# Qwiic_Alphanumeric_Display.net
KiCad netlist of a schematic drawn in EAGLE
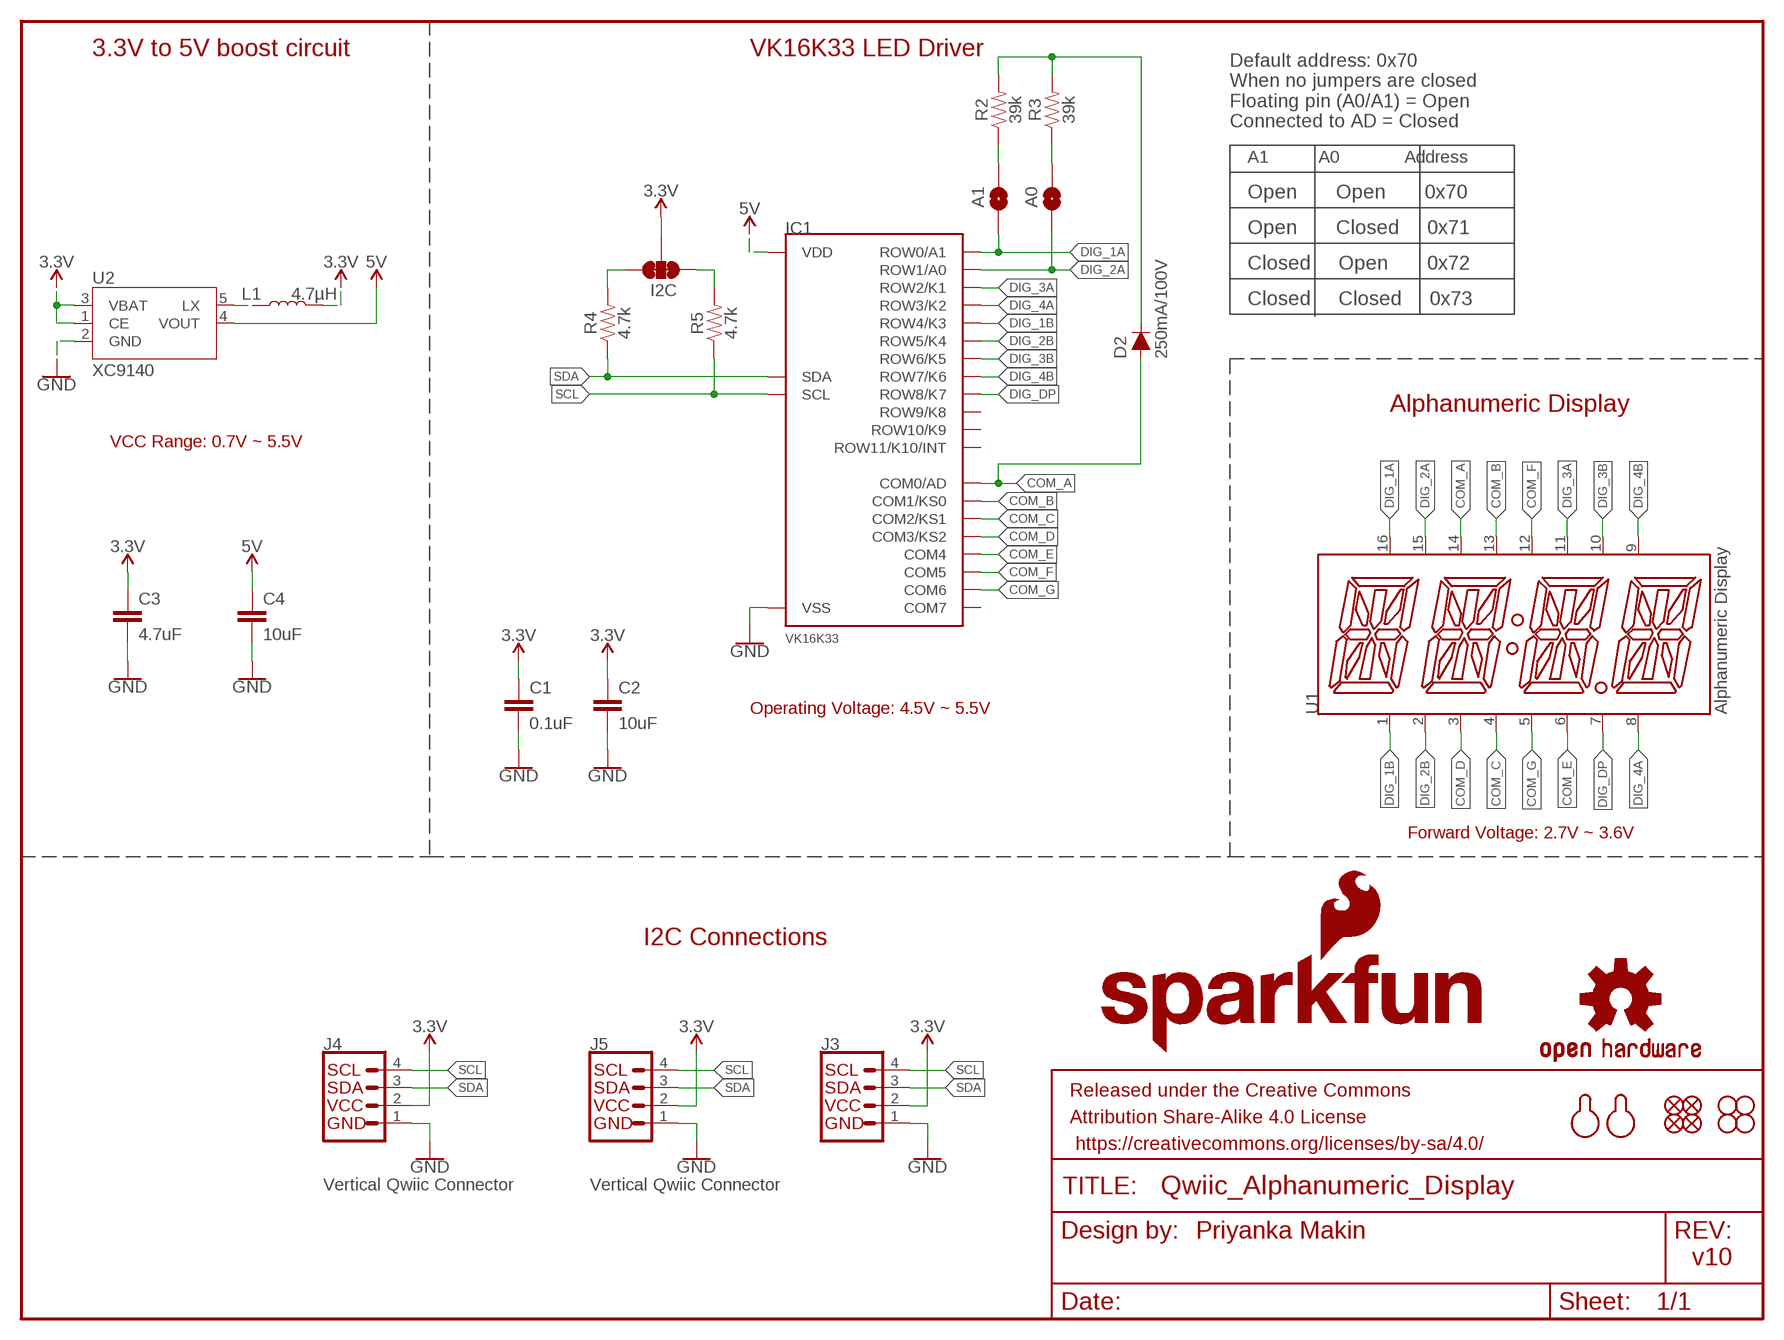
[diagram p0: schematic, sheet 1]

(export (version "E")
  (design (tool "Eeschema 10.0.6"))
  (components
    (comp (ref "A0")
      (value "JUMPER-SMT_2_NO_SILK")
      (footprint "eagle-import:SMT-JUMPER_2_NO_SILK")
      (libsource (lib "eagle-import") (part "JUMPER-SMT_2_NO_SILK"))
    )
    (comp (ref "A1")
      (value "JUMPER-SMT_2_NO_SILK")
      (footprint "eagle-import:SMT-JUMPER_2_NO_SILK")
      (libsource (lib "eagle-import") (part "JUMPER-SMT_2_NO_SILK"))
    )
    (comp (ref "C1")
      (value "0.1uF")
      (footprint "eagle-import:0603")
      (libsource (lib "eagle-import") (part "0.1UF-0603-25V-5%"))
    )
    (comp (ref "C2")
      (value "10uF")
      (footprint "eagle-import:0603")
      (libsource (lib "eagle-import") (part "10UF-0603-6.3V-20%"))
    )
    (comp (ref "C3")
      (value "4.7uF")
      (footprint "eagle-import:0603")
      (libsource (lib "eagle-import") (part "4.7UF-0603-6.3V-(10%)"))
    )
    (comp (ref "C4")
      (value "10uF")
      (footprint "eagle-import:0603")
      (libsource (lib "eagle-import") (part "10UF-0603-6.3V-20%"))
    )
    (comp (ref "D2")
      (value "250mA/100V")
      (footprint "eagle-import:SOD-323")
      (libsource (lib "eagle-import") (part "DIODE-BAS16J"))
    )
    (comp (ref "FD1")
      (value "FIDUCIAL1X2")
      (footprint "eagle-import:FIDUCIAL-1X2")
      (libsource (lib "eagle-import") (part "FIDUCIAL1X2"))
    )
    (comp (ref "FD2")
      (value "FIDUCIAL1X2")
      (footprint "eagle-import:FIDUCIAL-1X2")
      (libsource (lib "eagle-import") (part "FIDUCIAL1X2"))
    )
    (comp (ref "FD3")
      (value "FIDUCIAL1X2")
      (footprint "eagle-import:FIDUCIAL-1X2")
      (libsource (lib "eagle-import") (part "FIDUCIAL1X2"))
    )
    (comp (ref "FD4")
      (value "FIDUCIAL1X2")
      (footprint "eagle-import:FIDUCIAL-1X2")
      (libsource (lib "eagle-import") (part "FIDUCIAL1X2"))
    )
    (comp (ref "FRAME1")
      (value "FRAME-LETTER")
      (footprint "eagle-import:CREATIVE_COMMONS")
      (libsource (lib "eagle-import") (part "FRAME-LETTER"))
    )
    (comp (ref "H1")
      (value "STAND-OFF")
      (footprint "eagle-import:STAND-OFF")
      (libsource (lib "eagle-import") (part "STAND-OFF"))
    )
    (comp (ref "H2")
      (value "STAND-OFF")
      (footprint "eagle-import:STAND-OFF")
      (libsource (lib "eagle-import") (part "STAND-OFF"))
    )
    (comp (ref "H3")
      (value "STAND-OFF")
      (footprint "eagle-import:STAND-OFF")
      (libsource (lib "eagle-import") (part "STAND-OFF"))
    )
    (comp (ref "H4")
      (value "STAND-OFF")
      (footprint "eagle-import:STAND-OFF")
      (libsource (lib "eagle-import") (part "STAND-OFF"))
    )
    (comp (ref "I2C")
      (value "JUMPER-SMT_3_2-NC_TRACE_NO-SILK")
      (footprint "eagle-import:SMT-JUMPER_3_2-NC_TRACE_NO-SILK")
      (libsource (lib "eagle-import") (part "JUMPER-SMT_3_2-NC_TRACE_NO-SILK"))
    )
    (comp (ref "IC1")
      (value "VK16K33VK16K33")
      (footprint "eagle-import:VK16K33")
      (libsource (lib "eagle-import") (part "VK16K33VK16K33"))
    )
    (comp (ref "J3")
      (value "I2C_STANDARD_NO_SILK")
      (footprint "eagle-import:1X04_NO_SILK")
      (libsource (lib "eagle-import") (part "I2C_STANDARD_NO_SILK"))
    )
    (comp (ref "J4")
      (value "Vertical Qwiic Connector")
      (footprint "eagle-import:JST04_1MM_VERT")
      (libsource (lib "eagle-import") (part "QWIIC_CONNECTOR"))
    )
    (comp (ref "J5")
      (value "Vertical Qwiic Connector")
      (footprint "eagle-import:JST04_1MM_VERT")
      (libsource (lib "eagle-import") (part "QWIIC_CONNECTOR"))
    )
    (comp (ref "L1")
      (value "4.7µH")
      (footprint "eagle-import:INDUCTOR_4.7UH")
      (libsource (lib "eagle-import") (part "INDUCTOR-CDRH-4.7UH"))
    )
    (comp (ref "LOGO1")
      (value "OSHW-LOGOMINI")
      (footprint "eagle-import:OSHW-LOGO-MINI")
      (libsource (lib "eagle-import") (part "OSHW-LOGOMINI"))
    )
    (comp (ref "LOGO2")
      (value "SFE_LOGO_NAME.1_INCH")
      (footprint "eagle-import:SFE_LOGO_NAME_.1")
      (libsource (lib "eagle-import") (part "SFE_LOGO_NAME.1_INCH"))
    )
    (comp (ref "LOGO3")
      (value "SFE_LOGO_NAME.1_INCH")
      (footprint "eagle-import:SFE_LOGO_NAME_.1")
      (libsource (lib "eagle-import") (part "SFE_LOGO_NAME.1_INCH"))
    )
    (comp (ref "LOGO4")
      (value "SFE_LOGO_FLAME.1_INCH")
      (footprint "eagle-import:SFE_LOGO_FLAME_.1")
      (libsource (lib "eagle-import") (part "SFE_LOGO_FLAME.1_INCH"))
    )
    (comp (ref "R2")
      (value "39k")
      (footprint "eagle-import:0603")
      (libsource (lib "eagle-import") (part "39KOHM-0603-1/10W-1%"))
    )
    (comp (ref "R3")
      (value "39k")
      (footprint "eagle-import:0603")
      (libsource (lib "eagle-import") (part "39KOHM-0603-1/10W-1%"))
    )
    (comp (ref "R4")
      (value "4.7k")
      (footprint "eagle-import:0402-TIGHT")
      (libsource (lib "eagle-import") (part "4.7KOHM-0402T-1/16W-1%"))
    )
    (comp (ref "R5")
      (value "4.7k")
      (footprint "eagle-import:0402-TIGHT")
      (libsource (lib "eagle-import") (part "4.7KOHM-0402T-1/16W-1%"))
    )
    (comp (ref "U$3")
      (value "MOUNTING_HOLE_M2-0.4X6")
      (footprint "eagle-import:MOUNTING_HOLE_M2-0.4X6")
      (libsource (lib "eagle-import") (part "MOUNTING_HOLE_M2-0.4X6"))
    )
    (comp (ref "U$7")
      (value "MOUNTING_HOLE_M2-0.4X6")
      (footprint "eagle-import:MOUNTING_HOLE_M2-0.4X6")
      (libsource (lib "eagle-import") (part "MOUNTING_HOLE_M2-0.4X6"))
    )
    (comp (ref "U1")
      (value "Alphanumeric Display")
      (footprint "eagle-import:SILSMART_DISPLAY")
      (fields (field (name "PROD_ID") "COMP-14892"))
      (libsource (lib "eagle-import") (part "SILSMART_DISPLAY-PINK"))
    )
    (comp (ref "U2")
      (value "XC9140")
      (footprint "eagle-import:SOT23-5")
      (libsource (lib "eagle-import") (part "XC9140"))
    )
  )
  (nets
    (net (code "1") (name "3.3V") (class "Default")
      (node (ref "C1") (pin "1") (pinfunction "1_1") (pintype "passive"))
      (node (ref "C2") (pin "1") (pinfunction "1_1") (pintype "passive"))
      (node (ref "C3") (pin "1") (pinfunction "1_1") (pintype "passive"))
      (node (ref "I2C") (pin "2") (pinfunction "2_2") (pintype "passive"))
      (node (ref "J3") (pin "2") (pinfunction "2_2") (pintype "power_in"))
      (node (ref "J4") (pin "2") (pinfunction "2_2") (pintype "power_in"))
      (node (ref "J5") (pin "2") (pinfunction "2_2") (pintype "power_in"))
      (node (ref "L1") (pin "P$2") (pinfunction "2_P$2") (pintype "passive"))
      (node (ref "U2") (pin "1") (pinfunction "CE_1") (pintype "input"))
      (node (ref "U2") (pin "3") (pinfunction "VBAT_3") (pintype "power_in"))
    )
    (net (code "2") (name "5V") (class "Default")
      (node (ref "C4") (pin "1") (pinfunction "1_1") (pintype "passive"))
      (node (ref "IC1") (pin "24") (pinfunction "VDD_24") (pintype "power_in"))
      (node (ref "U2") (pin "4") (pinfunction "VOUT_4") (pintype "output"))
    )
    (net (code "3") (name "COM_A") (class "Default")
      (node (ref "D2") (pin "A") (pinfunction "A_A") (pintype "passive"))
      (node (ref "IC1") (pin "2") (pinfunction "COM0/AD_2") (pintype "bidirectional"))
      (node (ref "U1") (pin "14") (pinfunction "COM_A_14") (pintype "bidirectional"))
    )
    (net (code "4") (name "COM_B") (class "Default")
      (node (ref "IC1") (pin "3") (pinfunction "COM1/KS0_3") (pintype "bidirectional"))
      (node (ref "U1") (pin "13") (pinfunction "COM_B_13") (pintype "bidirectional"))
    )
    (net (code "5") (name "COM_C") (class "Default")
      (node (ref "IC1") (pin "4") (pinfunction "COM2/KS1_4") (pintype "bidirectional"))
      (node (ref "U1") (pin "4") (pinfunction "COM_C_4") (pintype "bidirectional"))
    )
    (net (code "6") (name "COM_D") (class "Default")
      (node (ref "IC1") (pin "5") (pinfunction "COM3/KS2_5") (pintype "bidirectional"))
      (node (ref "U1") (pin "3") (pinfunction "COM_D_3") (pintype "bidirectional"))
    )
    (net (code "7") (name "COM_E") (class "Default")
      (node (ref "IC1") (pin "6") (pinfunction "COM4_6") (pintype "bidirectional"))
      (node (ref "U1") (pin "6") (pinfunction "COM_E_6") (pintype "bidirectional"))
    )
    (net (code "8") (name "COM_F") (class "Default")
      (node (ref "IC1") (pin "7") (pinfunction "COM5_7") (pintype "bidirectional"))
      (node (ref "U1") (pin "12") (pinfunction "COM_F_12") (pintype "bidirectional"))
    )
    (net (code "9") (name "COM_G") (class "Default")
      (node (ref "IC1") (pin "8") (pinfunction "COM6_8") (pintype "bidirectional"))
      (node (ref "U1") (pin "5") (pinfunction "COM_G1_5") (pintype "bidirectional"))
    )
    (net (code "10") (name "DIG_1A") (class "Default")
      (node (ref "A1") (pin "1") (pinfunction "1_1") (pintype "passive"))
      (node (ref "IC1") (pin "21") (pinfunction "ROW0/A1_21") (pintype "bidirectional"))
      (node (ref "U1") (pin "16") (pinfunction "DIG_1A_16") (pintype "bidirectional"))
    )
    (net (code "11") (name "DIG_1B") (class "Default")
      (node (ref "IC1") (pin "17") (pinfunction "ROW4/K3_17") (pintype "bidirectional"))
      (node (ref "U1") (pin "1") (pinfunction "DIG_1B_1") (pintype "bidirectional"))
    )
    (net (code "12") (name "DIG_2A") (class "Default")
      (node (ref "A0") (pin "1") (pinfunction "1_1") (pintype "passive"))
      (node (ref "IC1") (pin "20") (pinfunction "ROW1/A0_20") (pintype "bidirectional"))
      (node (ref "U1") (pin "15") (pinfunction "DIG_2A_15") (pintype "bidirectional"))
    )
    (net (code "13") (name "DIG_2B") (class "Default")
      (node (ref "IC1") (pin "16") (pinfunction "ROW5/K4_16") (pintype "bidirectional"))
      (node (ref "U1") (pin "2") (pinfunction "DIG_2B_2") (pintype "bidirectional"))
    )
    (net (code "14") (name "DIG_3A") (class "Default")
      (node (ref "IC1") (pin "19") (pinfunction "ROW2/K1_19") (pintype "bidirectional"))
      (node (ref "U1") (pin "11") (pinfunction "DIG_3A_11") (pintype "bidirectional"))
    )
    (net (code "15") (name "DIG_3B") (class "Default")
      (node (ref "IC1") (pin "15") (pinfunction "ROW6/K5_15") (pintype "bidirectional"))
      (node (ref "U1") (pin "10") (pinfunction "DIG_3B_10") (pintype "bidirectional"))
    )
    (net (code "16") (name "DIG_4A") (class "Default")
      (node (ref "IC1") (pin "18") (pinfunction "ROW3/K2_18") (pintype "bidirectional"))
      (node (ref "U1") (pin "8") (pinfunction "DIG_4A_8") (pintype "bidirectional"))
    )
    (net (code "17") (name "DIG_4B") (class "Default")
      (node (ref "IC1") (pin "14") (pinfunction "ROW7/K6_14") (pintype "bidirectional"))
      (node (ref "U1") (pin "9") (pinfunction "DIG_4B_9") (pintype "bidirectional"))
    )
    (net (code "18") (name "DIG_DP") (class "Default")
      (node (ref "IC1") (pin "13") (pinfunction "ROW8/K7_13") (pintype "bidirectional"))
      (node (ref "U1") (pin "7") (pinfunction "DIG_DP_7") (pintype "bidirectional"))
    )
    (net (code "19") (name "GND") (class "Default")
      (node (ref "C1") (pin "2") (pinfunction "2_2") (pintype "passive"))
      (node (ref "C2") (pin "2") (pinfunction "2_2") (pintype "passive"))
      (node (ref "C3") (pin "2") (pinfunction "2_2") (pintype "passive"))
      (node (ref "C4") (pin "2") (pinfunction "2_2") (pintype "passive"))
      (node (ref "IC1") (pin "1") (pinfunction "VSS_1") (pintype "bidirectional"))
      (node (ref "J3") (pin "1") (pinfunction "1_1") (pintype "power_in"))
      (node (ref "J4") (pin "1") (pinfunction "1_1") (pintype "power_in"))
      (node (ref "J5") (pin "1") (pinfunction "1_1") (pintype "power_in"))
      (node (ref "U2") (pin "2") (pinfunction "GND_2") (pintype "power_in"))
    )
    (net (code "20") (name "Net-(A0-Pad2)") (class "Default")
      (node (ref "A0") (pin "2") (pinfunction "2_2") (pintype "passive"))
      (node (ref "R3") (pin "1") (pinfunction "1_1") (pintype "passive"))
    )
    (net (code "21") (name "Net-(A1-Pad2)") (class "Default")
      (node (ref "A1") (pin "2") (pinfunction "2_2") (pintype "passive"))
      (node (ref "R2") (pin "1") (pinfunction "1_1") (pintype "passive"))
    )
    (net (code "22") (name "Net-(D2-PadC)") (class "Default")
      (node (ref "D2") (pin "C") (pinfunction "C_C") (pintype "passive"))
      (node (ref "R2") (pin "2") (pinfunction "2_2") (pintype "passive"))
      (node (ref "R3") (pin "2") (pinfunction "2_2") (pintype "passive"))
    )
    (net (code "23") (name "Net-(I2C-Pad1)") (class "Default")
      (node (ref "I2C") (pin "1") (pinfunction "1_1") (pintype "passive"))
      (node (ref "R5") (pin "2") (pinfunction "2_2") (pintype "passive"))
    )
    (net (code "24") (name "Net-(I2C-Pad3)") (class "Default")
      (node (ref "I2C") (pin "3") (pinfunction "3_3") (pintype "passive"))
      (node (ref "R4") (pin "2") (pinfunction "2_2") (pintype "passive"))
    )
    (net (code "25") (name "Net-(L1-1)") (class "Default")
      (node (ref "L1") (pin "P$1") (pinfunction "1_P$1") (pintype "passive"))
      (node (ref "U2") (pin "5") (pinfunction "LX_5") (pintype "input"))
    )
    (net (code "26") (name "SCL") (class "Default")
      (node (ref "IC1") (pin "22") (pinfunction "SCL_22") (pintype "bidirectional"))
      (node (ref "J3") (pin "4") (pinfunction "4_4") (pintype "passive"))
      (node (ref "J4") (pin "4") (pinfunction "4_4") (pintype "passive"))
      (node (ref "J5") (pin "4") (pinfunction "4_4") (pintype "passive"))
      (node (ref "R5") (pin "1") (pinfunction "1_1") (pintype "passive"))
    )
    (net (code "27") (name "SDA") (class "Default")
      (node (ref "IC1") (pin "23") (pinfunction "SDA_23") (pintype "bidirectional"))
      (node (ref "J3") (pin "3") (pinfunction "3_3") (pintype "passive"))
      (node (ref "J4") (pin "3") (pinfunction "3_3") (pintype "passive"))
      (node (ref "J5") (pin "3") (pinfunction "3_3") (pintype "passive"))
      (node (ref "R4") (pin "1") (pinfunction "1_1") (pintype "passive"))
    )
    (net (code "28") (name "unconnected-(IC1-COM7-Pad9)") (class "Default")
      (node (ref "IC1") (pin "9") (pinfunction "COM7_9") (pintype "bidirectional"))
    )
    (net (code "29") (name "unconnected-(IC1-ROW9{slash}K8-Pad12)") (class "Default")
      (node (ref "IC1") (pin "12") (pinfunction "ROW9/K8_12") (pintype "bidirectional"))
    )
    (net (code "30") (name "unconnected-(IC1-ROW10{slash}K9-Pad11)") (class "Default")
      (node (ref "IC1") (pin "11") (pinfunction "ROW10/K9_11") (pintype "bidirectional"))
    )
    (net (code "31") (name "unconnected-(IC1-ROW11{slash}K10{slash}INT-Pad10)") (class "Default")
      (node (ref "IC1") (pin "10") (pinfunction "ROW11/K10/INT_10") (pintype "bidirectional"))
    )
  )
)
